# daq_daughter.net
KiCad netlist of a schematic drawn in EAGLE
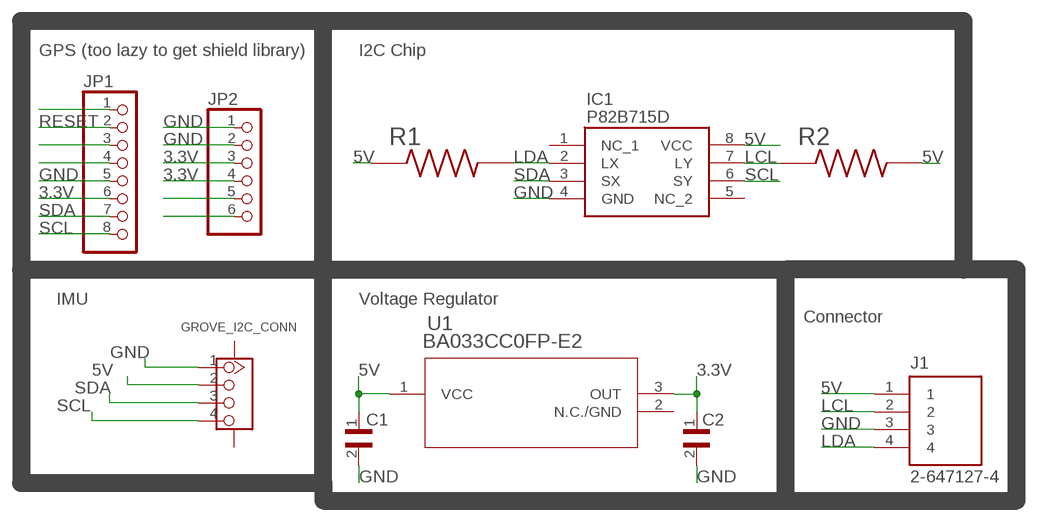
[diagram p0: schematic, sheet 1]

(export (version "E")
  (design (tool "Eeschema 10.0.6"))
  (components
    (comp (ref "C1")
      (value "C3216X5R1E106M085AC")
      (footprint "eagle-import:CAPC3216X100N")
      (fields (field (name "DIGI-KEY_PART_NUMBER") "445-14678-1-ND") (field (name "MF") "TDK"))
      (libsource (lib "eagle-import") (part "C3216X5R1E106M085AC"))
    )
    (comp (ref "C2")
      (value "C3216X5R1E106M085AC")
      (footprint "eagle-import:CAPC3216X100N")
      (fields (field (name "DIGI-KEY_PART_NUMBER") "445-14678-1-ND") (field (name "MF") "TDK"))
      (libsource (lib "eagle-import") (part "C3216X5R1E106M085AC"))
    )
    (comp (ref "GROVE_I2C_CONN")
      (value "CONNECTOR-NEW_GROVE-CONNECTOR-SMDDD")
      (footprint "eagle-import:CONNECTOR-NEW_HW4-SMD-2.0")
      (libsource (lib "eagle-import") (part "CONNECTOR-NEW_GROVE-CONNECTOR-SMDDD"))
    )
    (comp (ref "IC1")
      (value "P82B715D")
      (footprint "eagle-import:SOIC127P600X175-8N")
      (fields (field (name "MOUSER_PART_NUMBER") "595-P82B715D"))
      (libsource (lib "eagle-import") (part "P82B715D"))
    )
    (comp (ref "J1")
      (value "2-647127-4")
      (footprint "eagle-import:TE_2-647127-4")
      (fields (field (name "DIGI-KEY_PART_NUMBER") "A122823-ND") (field (name "MF") "TE Connectivity"))
      (libsource (lib "eagle-import") (part "2-647127-4"))
    )
    (comp (ref "JP1")
      (value "PINHD-1X8M")
      (footprint "eagle-import:1X08M")
      (libsource (lib "eagle-import") (part "PINHD-1X8M"))
    )
    (comp (ref "JP2")
      (value "PINHD-1X6M")
      (footprint "eagle-import:1X06M")
      (libsource (lib "eagle-import") (part "PINHD-1X6M"))
    )
    (comp (ref "R1")
      (value "RMCF1206JT10K0")
      (footprint "eagle-import:RESC3216X70N")
      (fields
        (field (name "DIGI-KEY_PART_NUMBER") "RMCF1206JT10K0CT-ND")
        (field (name "MF") "Stackpole Electronics Inc")
      )
      (libsource (lib "eagle-import") (part "RMCF1206JT10K0"))
    )
    (comp (ref "R2")
      (value "RMCF1206JT10K0")
      (footprint "eagle-import:RESC3216X70N")
      (fields
        (field (name "DIGI-KEY_PART_NUMBER") "RMCF1206JT10K0CT-ND")
        (field (name "MF") "Stackpole Electronics Inc")
      )
      (libsource (lib "eagle-import") (part "RMCF1206JT10K0"))
    )
    (comp (ref "U1")
      (value "BA033CC0FP-E2")
      (footprint "eagle-import:TO252-3_ROM")
      (fields (field (name "COPYRIGHT") "Copyright (C) 2022 Ultra Librarian. All rights reserved."))
      (libsource (lib "eagle-import") (part "BA033CC0FP-E2"))
    )
  )
  (nets
    (net (code "1") (name "/3.3V") (class "Default")
      (node (ref "C2") (pin "1") (pinfunction "1_1") (pintype "passive"))
      (node (ref "JP1") (pin "6") (pinfunction "6_6") (pintype "passive"))
      (node (ref "JP2") (pin "3") (pinfunction "3_3") (pintype "passive"))
      (node (ref "JP2") (pin "4") (pinfunction "4_4") (pintype "passive"))
      (node (ref "U1") (pin "3") (pinfunction "OUT_3") (pintype "output"))
    )
    (net (code "2") (name "/5V") (class "Default")
      (node (ref "C1") (pin "1") (pinfunction "1_1") (pintype "passive"))
      (node (ref "GROVE_I2C_CONN") (pin "2") (pinfunction "2_2") (pintype "bidirectional"))
      (node (ref "IC1") (pin "8") (pinfunction "VCC_8") (pintype "bidirectional"))
      (node (ref "J1") (pin "1") (pinfunction "1_1") (pintype "passive"))
      (node (ref "R1") (pin "1") (pinfunction "1_1") (pintype "passive"))
      (node (ref "R2") (pin "2") (pinfunction "2_2") (pintype "passive"))
      (node (ref "U1") (pin "1") (pinfunction "VCC_1") (pintype "power_in"))
    )
    (net (code "3") (name "/GND") (class "Default")
      (node (ref "C1") (pin "2") (pinfunction "2_2") (pintype "passive"))
      (node (ref "C2") (pin "2") (pinfunction "2_2") (pintype "passive"))
      (node (ref "GROVE_I2C_CONN") (pin "1") (pinfunction "1_1") (pintype "bidirectional"))
      (node (ref "IC1") (pin "4") (pinfunction "GND_4") (pintype "bidirectional"))
      (node (ref "J1") (pin "3") (pinfunction "3_3") (pintype "passive"))
      (node (ref "JP1") (pin "5") (pinfunction "5_5") (pintype "passive"))
      (node (ref "JP2") (pin "1") (pinfunction "1_1") (pintype "passive"))
      (node (ref "JP2") (pin "2") (pinfunction "2_2") (pintype "passive"))
    )
    (net (code "4") (name "/LCL") (class "Default")
      (node (ref "IC1") (pin "7") (pinfunction "LY_7") (pintype "bidirectional"))
      (node (ref "J1") (pin "2") (pinfunction "2_2") (pintype "passive"))
      (node (ref "R2") (pin "1") (pinfunction "1_1") (pintype "passive"))
    )
    (net (code "5") (name "/LDA") (class "Default")
      (node (ref "IC1") (pin "2") (pinfunction "LX_2") (pintype "bidirectional"))
      (node (ref "J1") (pin "4") (pinfunction "4_4") (pintype "passive"))
      (node (ref "R1") (pin "2") (pinfunction "2_2") (pintype "passive"))
    )
    (net (code "6") (name "/RESET") (class "Default")
      (node (ref "JP1") (pin "2") (pinfunction "2_2") (pintype "passive"))
    )
    (net (code "7") (name "/SCL") (class "Default")
      (node (ref "GROVE_I2C_CONN") (pin "4") (pinfunction "4_4") (pintype "bidirectional"))
      (node (ref "IC1") (pin "6") (pinfunction "SY_6") (pintype "bidirectional"))
      (node (ref "JP1") (pin "8") (pinfunction "8_8") (pintype "passive"))
    )
    (net (code "8") (name "/SDA") (class "Default")
      (node (ref "GROVE_I2C_CONN") (pin "3") (pinfunction "3_3") (pintype "bidirectional"))
      (node (ref "IC1") (pin "3") (pinfunction "SX_3") (pintype "bidirectional"))
      (node (ref "JP1") (pin "7") (pinfunction "7_7") (pintype "passive"))
    )
    (net (code "9") (name "unconnected-(GROVE_I2C_CONN-PadSS1)") (class "Default")
      (node (ref "GROVE_I2C_CONN") (pin "SS1") (pinfunction "SS1_SS1") (pintype "bidirectional"))
    )
    (net (code "10") (name "unconnected-(GROVE_I2C_CONN-PadSS2)") (class "Default")
      (node (ref "GROVE_I2C_CONN") (pin "SS2") (pinfunction "SS2_SS2") (pintype "bidirectional"))
    )
    (net (code "11") (name "unconnected-(IC1-NC_1-Pad1)") (class "Default")
      (node (ref "IC1") (pin "1") (pinfunction "NC_1_1") (pintype "bidirectional"))
    )
    (net (code "12") (name "unconnected-(IC1-NC_2-Pad5)") (class "Default")
      (node (ref "IC1") (pin "5") (pinfunction "NC_2_5") (pintype "bidirectional"))
    )
    (net (code "13") (name "unconnected-(JP1-Pad1)") (class "Default")
      (node (ref "JP1") (pin "1") (pinfunction "1_1") (pintype "passive"))
    )
    (net (code "14") (name "unconnected-(JP1-Pad3)") (class "Default")
      (node (ref "JP1") (pin "3") (pinfunction "3_3") (pintype "passive"))
    )
    (net (code "15") (name "unconnected-(JP1-Pad4)") (class "Default")
      (node (ref "JP1") (pin "4") (pinfunction "4_4") (pintype "passive"))
    )
    (net (code "16") (name "unconnected-(JP2-Pad5)") (class "Default")
      (node (ref "JP2") (pin "5") (pinfunction "5_5") (pintype "passive"))
    )
    (net (code "17") (name "unconnected-(JP2-Pad6)") (class "Default")
      (node (ref "JP2") (pin "6") (pinfunction "6_6") (pintype "passive"))
    )
    (net (code "18") (name "unconnected-(U1-N.C.{slash}GND-Pad2)") (class "Default")
      (node (ref "U1") (pin "2") (pinfunction "N.C./GND_2") (pintype "no_connect"))
    )
  )
)
